# conv_smd.net
KiCad netlist of a schematic drawn in EAGLE
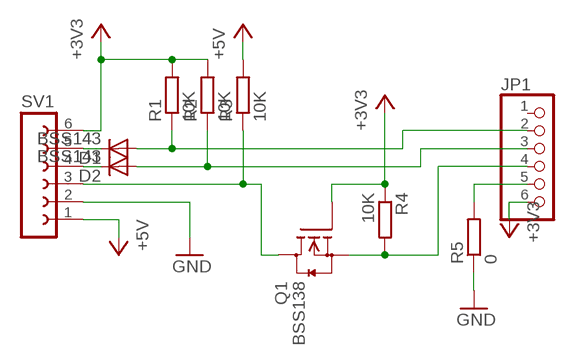
[diagram p0: schematic, sheet 1]

(export (version "E")
  (design (tool "Eeschema 10.0.6"))
  (components
    (comp (ref "D1")
      (value "BSS143")
      (footprint "eagle-import:SOD80C")
      (libsource (lib "eagle-import") (part "DIODE-SOD80C"))
    )
    (comp (ref "D2")
      (value "BSS143")
      (footprint "eagle-import:SOD80C")
      (libsource (lib "eagle-import") (part "DIODE-SOD80C"))
    )
    (comp (ref "JP1")
      (value "PINHD-1X6/90")
      (footprint "eagle-import:1X06_90")
      (libsource (lib "eagle-import") (part "PINHD-1X6/90"))
    )
    (comp (ref "Q1")
      (value "BSS138")
      (footprint "eagle-import:SOT23")
      (libsource (lib "eagle-import") (part "BSS138"))
    )
    (comp (ref "R1")
      (value "10K")
      (footprint "eagle-import:M0805")
      (libsource (lib "eagle-import") (part "R-EU_M0805"))
    )
    (comp (ref "R2")
      (value "10K")
      (footprint "eagle-import:M0805")
      (libsource (lib "eagle-import") (part "R-EU_M0805"))
    )
    (comp (ref "R3")
      (value "10K")
      (footprint "eagle-import:M1206")
      (libsource (lib "eagle-import") (part "R-EU_M1206"))
    )
    (comp (ref "R4")
      (value "10K")
      (footprint "eagle-import:M0805")
      (libsource (lib "eagle-import") (part "R-EU_M0805"))
    )
    (comp (ref "R5")
      (value "0")
      (footprint "eagle-import:M1206")
      (libsource (lib "eagle-import") (part "R-EU_M1206"))
    )
    (comp (ref "SV1")
      (value "FE06W")
      (footprint "eagle-import:FE06W")
      (libsource (lib "eagle-import") (part "FE06W"))
    )
  )
  (nets
    (net (code "1") (name "+3V3") (class "Default")
      (node (ref "JP1") (pin "6") (pinfunction "6_6") (pintype "passive"))
      (node (ref "Q1") (pin "1") (pinfunction "G_1") (pintype "passive"))
      (node (ref "R1") (pin "2") (pinfunction "2_2") (pintype "passive"))
      (node (ref "R2") (pin "2") (pinfunction "2_2") (pintype "passive"))
      (node (ref "R4") (pin "1") (pinfunction "1_1") (pintype "passive"))
      (node (ref "SV1") (pin "6") (pinfunction "6_6") (pintype "passive"))
    )
    (net (code "2") (name "+5V") (class "Default")
      (node (ref "R3") (pin "2") (pinfunction "2_2") (pintype "passive"))
      (node (ref "SV1") (pin "1") (pinfunction "1_1") (pintype "passive"))
    )
    (net (code "3") (name "GND") (class "Default")
      (node (ref "R5") (pin "1") (pinfunction "1_1") (pintype "passive"))
      (node (ref "SV1") (pin "2") (pinfunction "2_2") (pintype "passive"))
    )
    (net (code "4") (name "Net-(D1-PadA)") (class "Default")
      (node (ref "D1") (pin "A") (pinfunction "A_A") (pintype "passive"))
      (node (ref "JP1") (pin "2") (pinfunction "2_2") (pintype "passive"))
      (node (ref "R1") (pin "1") (pinfunction "1_1") (pintype "passive"))
    )
    (net (code "5") (name "Net-(D1-PadC)") (class "Default")
      (node (ref "D1") (pin "C") (pinfunction "C_C") (pintype "passive"))
      (node (ref "SV1") (pin "5") (pinfunction "5_5") (pintype "passive"))
    )
    (net (code "6") (name "Net-(D2-PadA)") (class "Default")
      (node (ref "D2") (pin "A") (pinfunction "A_A") (pintype "passive"))
      (node (ref "JP1") (pin "3") (pinfunction "3_3") (pintype "passive"))
      (node (ref "R2") (pin "1") (pinfunction "1_1") (pintype "passive"))
    )
    (net (code "7") (name "Net-(D2-PadC)") (class "Default")
      (node (ref "D2") (pin "C") (pinfunction "C_C") (pintype "passive"))
      (node (ref "SV1") (pin "4") (pinfunction "4_4") (pintype "passive"))
    )
    (net (code "8") (name "Net-(JP1-Pad5)") (class "Default")
      (node (ref "JP1") (pin "5") (pinfunction "5_5") (pintype "passive"))
      (node (ref "R5") (pin "2") (pinfunction "2_2") (pintype "passive"))
    )
    (net (code "9") (name "Net-(Q1-D)") (class "Default")
      (node (ref "Q1") (pin "3") (pinfunction "D_3") (pintype "passive"))
      (node (ref "R3") (pin "1") (pinfunction "1_1") (pintype "passive"))
      (node (ref "SV1") (pin "3") (pinfunction "3_3") (pintype "passive"))
    )
    (net (code "10") (name "Net-(Q1-S)") (class "Default")
      (node (ref "JP1") (pin "4") (pinfunction "4_4") (pintype "passive"))
      (node (ref "Q1") (pin "2") (pinfunction "S_2") (pintype "passive"))
      (node (ref "R4") (pin "2") (pinfunction "2_2") (pintype "passive"))
    )
    (net (code "11") (name "unconnected-(JP1-Pad1)") (class "Default")
      (node (ref "JP1") (pin "1") (pinfunction "1_1") (pintype "passive"))
    )
  )
)
